# zx-ExternalROM.net
KiCad netlist of a schematic drawn in Altium Designer
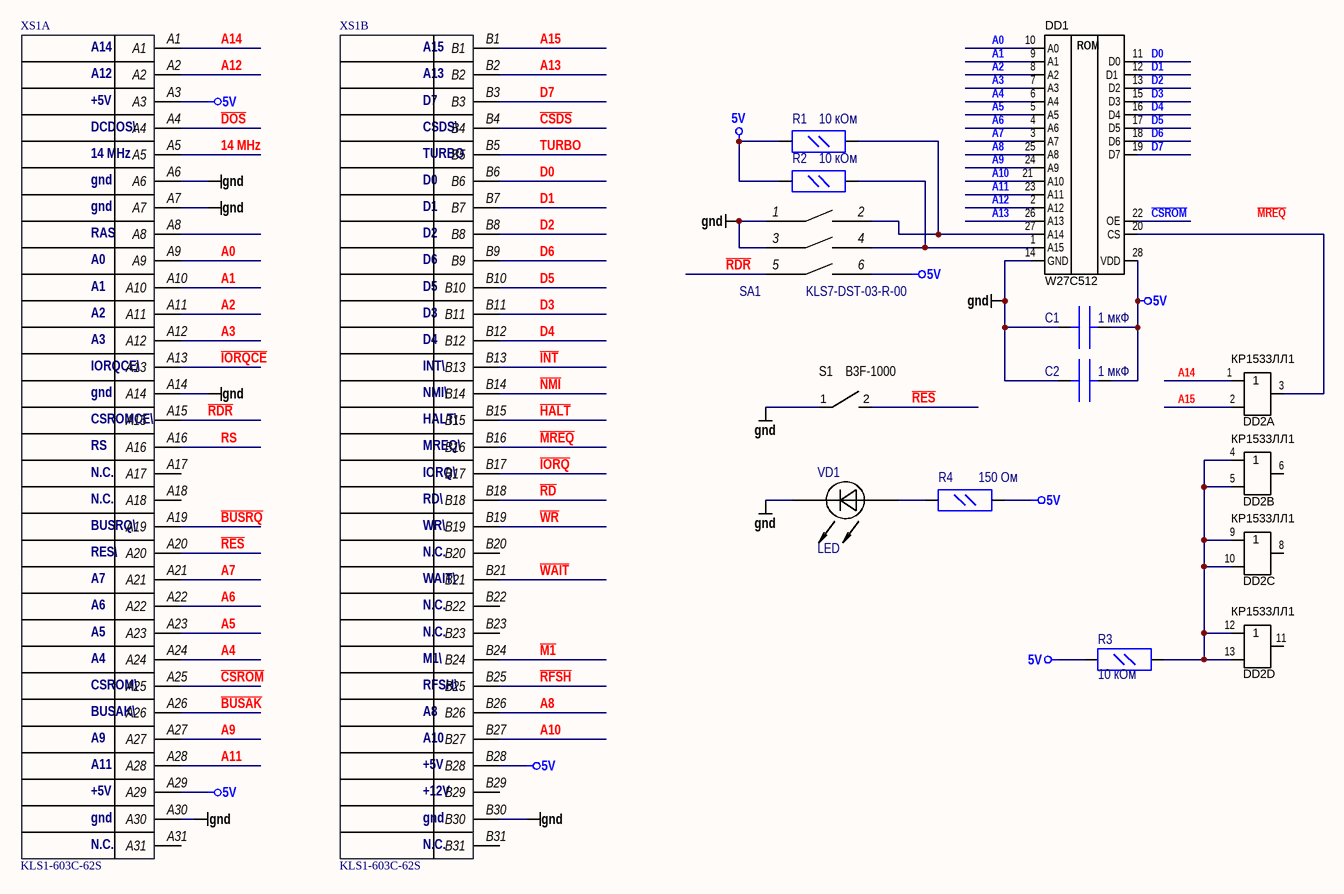
[diagram p0: zx-ExternalROM.SchDoc]

(export (version "E")
  (design (tool "Eeschema 10.0.6"))
  (components
    (comp (ref "C1")
      (value "1 мкФ")
      (footprint "CAP C 3216 (1206) 1.9h")
      (description "Конденсатор не полярный")
      (fields (field (name "PART NUMBER") "CC1206KKX5R9BB105") (field (name "VOLTAGE") "50"))
      (libsource (lib "Capacitor_chip 1206$") (part "ЧИП-1206-X5R-1 мкФ 50В ±10%"))
    )
    (comp (ref "C2")
      (value "1 мкФ")
      (footprint "CAP C 3216 (1206) 1.9h")
      (description "Конденсатор не полярный")
      (fields (field (name "PART NUMBER") "CC1206KKX5R9BB105") (field (name "VOLTAGE") "50"))
      (libsource (lib "Capacitor_chip 1206$") (part "ЧИП-1206-X5R-1 мкФ 50В ±10%"))
    )
    (comp (ref "DD1") (value "W27C512") (footprint "ZIF-28") (libsource (lib "ROM") (part "W27C512")))
    (comp (ref "DD2") (value "КР1533ЛЛ1") (footprint "DIP14") (libsource (lib "logic") (part "КР1533ЛЛ1")))
    (comp (ref "R1")
      (value "10 кОм")
      (footprint "RES C 2012 (0805) 0.65h")
      (description "Резистор 0.125 Вт")
      (fields (field (name "PART NUMBER") "RC0805JR-0710KL") (field (name "TOLERANCE") "±5%"))
      (libsource (lib "Resistor_chip 0805$") (part "ЧИП-0805-10 кОм ±5%"))
    )
    (comp (ref "R2")
      (value "10 кОм")
      (footprint "RES C 2012 (0805) 0.65h")
      (description "Резистор 0.125 Вт")
      (fields (field (name "PART NUMBER") "RC0805JR-0710KL") (field (name "TOLERANCE") "±5%"))
      (libsource (lib "Resistor_chip 0805$") (part "ЧИП-0805-10 кОм ±5%"))
    )
    (comp (ref "R3")
      (value "10 кОм")
      (footprint "RES C 2012 (0805) 0.65h")
      (description "Резистор 0.125 Вт")
      (fields (field (name "PART NUMBER") "RC0805JR-0710KL") (field (name "TOLERANCE") "±5%"))
      (libsource (lib "Resistor_chip 0805$") (part "ЧИП-0805-10 кОм ±5%"))
    )
    (comp (ref "R4")
      (value "150 Ом")
      (footprint "RES C 2012 (0805) 0.65h")
      (description "Резистор 0.125 Вт")
      (fields (field (name "PART NUMBER") "RC0805JR-07150RL") (field (name "TOLERANCE") "±5%"))
      (libsource (lib "Resistor_chip 0805$") (part "ЧИП-0805-150 Ом ±5%"))
    )
    (comp (ref "S1")
      (value "B3F-1000")
      (footprint "SW_B3F-1000")
      (libsource (lib "Buttons") (part "B3F-1000"))
    )
    (comp (ref "SA1")
      (value "KLS7-DST-03-R-00")
      (footprint "KLS7-DST-03-R-00")
      (description "Переключатель 3-х позиционный")
      (libsource (lib "gst") (part "KLS7-DST-03-R-00"))
    )
    (comp (ref "VD1") (value "LED") (footprint "LED 3mm") (libsource (lib "ipa") (part "LED")))
    (comp (ref "XS1")
      (value "KLS1-603C-62S")
      (footprint "KLS1-603 ISA")
      (libsource (lib "gst") (part "KLS1-603C-64S"))
    )
  )
  (nets
    (net (code "1") (name "/14 MHz") (class "Default")
      (node (ref "XS1") (pin "A5") (pinfunction "A5_A5") (pintype "passive"))
    )
    (net (code "2") (name "/A0") (class "Default")
      (node (ref "DD1") (pin "10") (pinfunction "A0_10") (pintype "passive"))
      (node (ref "XS1") (pin "A9") (pinfunction "A9_A9") (pintype "passive"))
    )
    (net (code "3") (name "/A1") (class "Default")
      (node (ref "DD1") (pin "9") (pinfunction "A1_9") (pintype "passive"))
      (node (ref "XS1") (pin "A10") (pinfunction "A10_A10") (pintype "passive"))
    )
    (net (code "4") (name "/A2") (class "Default")
      (node (ref "DD1") (pin "8") (pinfunction "A2_8") (pintype "passive"))
      (node (ref "XS1") (pin "A11") (pinfunction "A11_A11") (pintype "passive"))
    )
    (net (code "5") (name "/A3") (class "Default")
      (node (ref "DD1") (pin "7") (pinfunction "A3_7") (pintype "passive"))
      (node (ref "XS1") (pin "A12") (pinfunction "A12_A12") (pintype "passive"))
    )
    (net (code "6") (name "/A4") (class "Default")
      (node (ref "DD1") (pin "6") (pinfunction "A4_6") (pintype "passive"))
      (node (ref "XS1") (pin "A24") (pinfunction "A24_A24") (pintype "passive"))
    )
    (net (code "7") (name "/A5") (class "Default")
      (node (ref "DD1") (pin "5") (pinfunction "A5_5") (pintype "passive"))
      (node (ref "XS1") (pin "A23") (pinfunction "A23_A23") (pintype "passive"))
    )
    (net (code "8") (name "/A6") (class "Default")
      (node (ref "DD1") (pin "4") (pinfunction "A6_4") (pintype "passive"))
      (node (ref "XS1") (pin "A22") (pinfunction "A22_A22") (pintype "passive"))
    )
    (net (code "9") (name "/A7") (class "Default")
      (node (ref "DD1") (pin "3") (pinfunction "A7_3") (pintype "passive"))
      (node (ref "XS1") (pin "A21") (pinfunction "A21_A21") (pintype "passive"))
    )
    (net (code "10") (name "/A8") (class "Default")
      (node (ref "DD1") (pin "25") (pinfunction "A8_25") (pintype "passive"))
      (node (ref "XS1") (pin "B26") (pinfunction "B26_B26") (pintype "passive"))
    )
    (net (code "11") (name "/A9") (class "Default")
      (node (ref "DD1") (pin "24") (pinfunction "A9_24") (pintype "passive"))
      (node (ref "XS1") (pin "A27") (pinfunction "A27_A27") (pintype "passive"))
    )
    (net (code "12") (name "/A10") (class "Default")
      (node (ref "DD1") (pin "21") (pinfunction "A10_21") (pintype "passive"))
      (node (ref "XS1") (pin "B27") (pinfunction "B27_B27") (pintype "passive"))
    )
    (net (code "13") (name "/A11") (class "Default")
      (node (ref "DD1") (pin "23") (pinfunction "A11_23") (pintype "passive"))
      (node (ref "XS1") (pin "A28") (pinfunction "A28_A28") (pintype "passive"))
    )
    (net (code "14") (name "/A12") (class "Default")
      (node (ref "DD1") (pin "2") (pinfunction "A12_2") (pintype "passive"))
      (node (ref "XS1") (pin "A2") (pinfunction "A2_A2") (pintype "passive"))
    )
    (net (code "15") (name "/A13") (class "Default")
      (node (ref "DD1") (pin "26") (pinfunction "A13_26") (pintype "passive"))
      (node (ref "XS1") (pin "B2") (pinfunction "B2_B2") (pintype "passive"))
    )
    (net (code "16") (name "/A14") (class "Default")
      (node (ref "DD2") (pin "1") (pintype "passive"))
      (node (ref "XS1") (pin "A1") (pinfunction "A1_A1") (pintype "passive"))
    )
    (net (code "17") (name "/A15") (class "Default")
      (node (ref "DD2") (pin "2") (pintype "passive"))
      (node (ref "XS1") (pin "B1") (pinfunction "B1_B1") (pintype "passive"))
    )
    (net (code "18") (name "/D0") (class "Default")
      (node (ref "DD1") (pin "11") (pinfunction "D0_11") (pintype "passive"))
      (node (ref "XS1") (pin "B6") (pinfunction "B6_B6") (pintype "passive"))
    )
    (net (code "19") (name "/D1") (class "Default")
      (node (ref "DD1") (pin "12") (pinfunction "D1_12") (pintype "passive"))
      (node (ref "XS1") (pin "B7") (pinfunction "B7_B7") (pintype "passive"))
    )
    (net (code "20") (name "/D2") (class "Default")
      (node (ref "DD1") (pin "13") (pinfunction "D2_13") (pintype "passive"))
      (node (ref "XS1") (pin "B8") (pinfunction "B8_B8") (pintype "passive"))
    )
    (net (code "21") (name "/D3") (class "Default")
      (node (ref "DD1") (pin "15") (pinfunction "D3_15") (pintype "passive"))
      (node (ref "XS1") (pin "B11") (pinfunction "B11_B11") (pintype "passive"))
    )
    (net (code "22") (name "/D4") (class "Default")
      (node (ref "DD1") (pin "16") (pinfunction "D4_16") (pintype "passive"))
      (node (ref "XS1") (pin "B12") (pinfunction "B12_B12") (pintype "passive"))
    )
    (net (code "23") (name "/D5") (class "Default")
      (node (ref "DD1") (pin "17") (pinfunction "D5_17") (pintype "passive"))
      (node (ref "XS1") (pin "B10") (pinfunction "B10_B10") (pintype "passive"))
    )
    (net (code "24") (name "/D6") (class "Default")
      (node (ref "DD1") (pin "18") (pinfunction "D6_18") (pintype "passive"))
      (node (ref "XS1") (pin "B9") (pinfunction "B9_B9") (pintype "passive"))
    )
    (net (code "25") (name "/D7") (class "Default")
      (node (ref "DD1") (pin "19") (pinfunction "D7_19") (pintype "passive"))
      (node (ref "XS1") (pin "B3") (pinfunction "B3_B3") (pintype "passive"))
    )
    (net (code "26") (name "/RS") (class "Default")
      (node (ref "XS1") (pin "A16") (pinfunction "A16_A16") (pintype "passive"))
    )
    (net (code "27") (name "/TURBO") (class "Default")
      (node (ref "XS1") (pin "B5") (pinfunction "B5_B5") (pintype "passive"))
    )
    (net (code "28") (name "/~{BUSAK}") (class "Default")
      (node (ref "XS1") (pin "A26") (pinfunction "A26_A26") (pintype "passive"))
    )
    (net (code "29") (name "/~{BUSRQ}") (class "Default")
      (node (ref "XS1") (pin "A19") (pinfunction "A19_A19") (pintype "passive"))
    )
    (net (code "30") (name "/~{CSDS}") (class "Default")
      (node (ref "XS1") (pin "B4") (pinfunction "B4_B4") (pintype "passive"))
    )
    (net (code "31") (name "/~{CSROM}") (class "Default")
      (node (ref "DD1") (pin "22") (pinfunction "OE_22") (pintype "passive"))
      (node (ref "XS1") (pin "A25") (pinfunction "A25_A25") (pintype "passive"))
    )
    (net (code "32") (name "/~{DOS}") (class "Default")
      (node (ref "XS1") (pin "A4") (pinfunction "A4_A4") (pintype "passive"))
    )
    (net (code "33") (name "/~{HALT}") (class "Default")
      (node (ref "XS1") (pin "B15") (pinfunction "B15_B15") (pintype "passive"))
    )
    (net (code "34") (name "/~{INT}") (class "Default")
      (node (ref "XS1") (pin "B13") (pinfunction "B13_B13") (pintype "passive"))
    )
    (net (code "35") (name "/~{IORQCE}") (class "Default")
      (node (ref "XS1") (pin "A13") (pinfunction "A13_A13") (pintype "passive"))
    )
    (net (code "36") (name "/~{IORQ}") (class "Default")
      (node (ref "XS1") (pin "B17") (pinfunction "B17_B17") (pintype "passive"))
    )
    (net (code "37") (name "/~{M1}") (class "Default")
      (node (ref "XS1") (pin "B24") (pinfunction "B24_B24") (pintype "passive"))
    )
    (net (code "38") (name "/~{MREQ}") (class "Default")
      (node (ref "XS1") (pin "B16") (pinfunction "B16_B16") (pintype "passive"))
    )
    (net (code "39") (name "/~{NMI}") (class "Default")
      (node (ref "XS1") (pin "B14") (pinfunction "B14_B14") (pintype "passive"))
    )
    (net (code "40") (name "/~{RDR}") (class "Default")
      (node (ref "SA1") (pin "5") (pinfunction "5_5") (pintype "passive"))
      (node (ref "XS1") (pin "A15") (pinfunction "A15_A15") (pintype "passive"))
    )
    (net (code "41") (name "/~{RD}") (class "Default")
      (node (ref "XS1") (pin "B18") (pinfunction "B18_B18") (pintype "passive"))
    )
    (net (code "42") (name "/~{RES}") (class "Default")
      (node (ref "S1") (pin "2") (pinfunction "1_2") (pintype "passive"))
      (node (ref "XS1") (pin "A20") (pinfunction "A20_A20") (pintype "passive"))
    )
    (net (code "43") (name "/~{RFSH}") (class "Default")
      (node (ref "XS1") (pin "B25") (pinfunction "B25_B25") (pintype "passive"))
    )
    (net (code "44") (name "/~{WAIT}") (class "Default")
      (node (ref "XS1") (pin "B21") (pinfunction "B21_B21") (pintype "passive"))
    )
    (net (code "45") (name "/~{WR}") (class "Default")
      (node (ref "XS1") (pin "B19") (pinfunction "B19_B19") (pintype "passive"))
    )
    (net (code "46") (name "5V") (class "Default")
      (node (ref "C1") (pin "1") (pinfunction "1_1") (pintype "passive"))
      (node (ref "C2") (pin "1") (pinfunction "1_1") (pintype "passive"))
      (node (ref "DD1") (pin "28") (pinfunction "VDD_28") (pintype "passive"))
      (node (ref "R1") (pin "1") (pinfunction "1_1") (pintype "passive"))
      (node (ref "R2") (pin "1") (pinfunction "1_1") (pintype "passive"))
      (node (ref "R3") (pin "1") (pinfunction "1_1") (pintype "passive"))
      (node (ref "R4") (pin "2") (pinfunction "2_2") (pintype "passive"))
      (node (ref "SA1") (pin "6") (pinfunction "6_6") (pintype "passive"))
      (node (ref "XS1") (pin "A29") (pinfunction "A29_A29") (pintype "passive"))
      (node (ref "XS1") (pin "A3") (pinfunction "A3_A3") (pintype "passive"))
      (node (ref "XS1") (pin "B28") (pinfunction "B28_B28") (pintype "passive"))
    )
    (net (code "47") (name "GND") (class "Default")
      (node (ref "DD2") (pin "7") (pinfunction "GND_7") (pintype "power_in"))
    )
    (net (code "48") (name "Net-(DD1-A14)") (class "Default")
      (node (ref "DD1") (pin "27") (pinfunction "A14_27") (pintype "passive"))
      (node (ref "R1") (pin "2") (pinfunction "2_2") (pintype "passive"))
      (node (ref "SA1") (pin "2") (pinfunction "2_2") (pintype "passive"))
    )
    (net (code "49") (name "Net-(DD1-A15)") (class "Default")
      (node (ref "DD1") (pin "1") (pinfunction "A15_1") (pintype "passive"))
      (node (ref "R2") (pin "2") (pinfunction "2_2") (pintype "passive"))
      (node (ref "SA1") (pin "4") (pinfunction "4_4") (pintype "passive"))
    )
    (net (code "50") (name "Net-(DD1-CS)") (class "Default")
      (node (ref "DD1") (pin "20") (pinfunction "CS_20") (pintype "passive"))
      (node (ref "DD2") (pin "3") (pintype "passive"))
    )
    (net (code "51") (name "Net-(DD2-Pad10)") (class "Default")
      (node (ref "DD2") (pin "10") (pintype "passive"))
      (node (ref "DD2") (pin "12") (pintype "passive"))
      (node (ref "DD2") (pin "13") (pintype "passive"))
      (node (ref "DD2") (pin "4") (pintype "passive"))
      (node (ref "DD2") (pin "5") (pintype "passive"))
      (node (ref "DD2") (pin "9") (pintype "passive"))
      (node (ref "R3") (pin "2") (pinfunction "2_2") (pintype "passive"))
    )
    (net (code "52") (name "Net-(R4-Pad1)") (class "Default")
      (node (ref "R4") (pin "1") (pinfunction "1_1") (pintype "passive"))
      (node (ref "VD1") (pin "2") (pinfunction "2_2") (pintype "passive"))
    )
    (net (code "53") (name "VCC") (class "Default")
      (node (ref "DD2") (pin "14") (pinfunction "VCC_14") (pintype "power_in"))
    )
    (net (code "54") (name "gnd") (class "Default")
      (node (ref "C1") (pin "2") (pinfunction "2_2") (pintype "passive"))
      (node (ref "C2") (pin "2") (pinfunction "2_2") (pintype "passive"))
      (node (ref "DD1") (pin "14") (pinfunction "GND_14") (pintype "passive"))
      (node (ref "S1") (pin "1") (pinfunction "0_1") (pintype "passive"))
      (node (ref "SA1") (pin "1") (pinfunction "1_1") (pintype "passive"))
      (node (ref "SA1") (pin "3") (pinfunction "3_3") (pintype "passive"))
      (node (ref "VD1") (pin "1") (pinfunction "1_1") (pintype "passive"))
      (node (ref "XS1") (pin "A14") (pinfunction "A14_A14") (pintype "passive"))
      (node (ref "XS1") (pin "A30") (pinfunction "A30_A30") (pintype "passive"))
      (node (ref "XS1") (pin "A6") (pinfunction "A6_A6") (pintype "passive"))
      (node (ref "XS1") (pin "A7") (pinfunction "A7_A7") (pintype "passive"))
      (node (ref "XS1") (pin "B30") (pinfunction "B30_B30") (pintype "passive"))
    )
    (net (code "55") (name "unconnected-(DD2-Pad6)") (class "Default")
      (node (ref "DD2") (pin "6") (pintype "passive"))
    )
    (net (code "56") (name "unconnected-(DD2-Pad8)") (class "Default")
      (node (ref "DD2") (pin "8") (pintype "passive"))
    )
    (net (code "57") (name "unconnected-(DD2-Pad11)") (class "Default")
      (node (ref "DD2") (pin "11") (pintype "passive"))
    )
    (net (code "58") (name "unconnected-(DD2-Pad14)") (class "Default")
      (node (ref "DD2") (pin "14") (pintype "passive"))
    )
    (net (code "59") (name "unconnected-(XS1-PadA8)") (class "Default")
      (node (ref "XS1") (pin "A8") (pinfunction "A8_A8") (pintype "passive"))
    )
    (net (code "60") (name "unconnected-(XS1-PadA17)") (class "Default")
      (node (ref "XS1") (pin "A17") (pinfunction "A17_A17") (pintype "passive"))
    )
    (net (code "61") (name "unconnected-(XS1-PadA18)") (class "Default")
      (node (ref "XS1") (pin "A18") (pinfunction "A18_A18") (pintype "passive"))
    )
    (net (code "62") (name "unconnected-(XS1-PadA31)") (class "Default")
      (node (ref "XS1") (pin "A31") (pinfunction "A31_A31") (pintype "passive"))
    )
    (net (code "63") (name "unconnected-(XS1-PadB20)") (class "Default")
      (node (ref "XS1") (pin "B20") (pinfunction "B20_B20") (pintype "passive"))
    )
    (net (code "64") (name "unconnected-(XS1-PadB22)") (class "Default")
      (node (ref "XS1") (pin "B22") (pinfunction "B22_B22") (pintype "passive"))
    )
    (net (code "65") (name "unconnected-(XS1-PadB23)") (class "Default")
      (node (ref "XS1") (pin "B23") (pinfunction "B23_B23") (pintype "passive"))
    )
    (net (code "66") (name "unconnected-(XS1-PadB29)") (class "Default")
      (node (ref "XS1") (pin "B29") (pinfunction "B29_B29") (pintype "passive"))
    )
    (net (code "67") (name "unconnected-(XS1-PadB31)") (class "Default")
      (node (ref "XS1") (pin "B31") (pinfunction "B31_B31") (pintype "passive"))
    )
  )
)
